# ADC-ANALOGUE_INPUT.net
KiCad netlist of a schematic drawn in Altium Designer
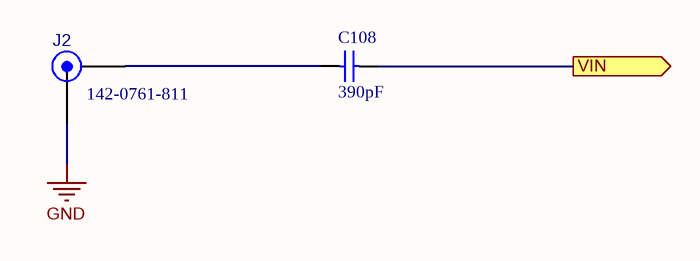
[diagram p0: ADC-ANALOGUE INPUT.SchDoc]

(export (version "E")
  (design (tool "Eeschema 10.0.6"))
  (components
    (comp (ref "C108")
      (value "390pF")
      (footprint "CAPC1005X55N")
      (description "Capacitor 0402 SMD")
      (fields (field (name "CREATED_BY") "EDA-ASA") (field (name "CHECKED_BY") "*"))
      (libsource (lib "EDA-Passive") (part "cap0402"))
    )
    (comp (ref "J2")
      (value "142-0761-811")
      (footprint "EDGE_LAUNCH_TH_SMA")
      (description "High Frequency SMA End Lauch Connector")
      (fields
        (field (name "MANUFACTURER") "JOHNSON")
        (field (name "MANUFACTURER_PN") "142-0761-811")
        (field (name "CREATED_BY") "CT")
        (field (name "CHECKED_BY") "*")
      )
      (libsource (lib "Charles-TEMP") (part "142-0761-811"))
    )
  )
  (nets
    (net (code "1") (name "/VIN") (class "Default")
      (node (ref "C108") (pin "2") (pinfunction "2_2") (pintype "passive"))
    )
    (net (code "2") (name "GND") (class "Default")
      (node (ref "J2") (pin "2") (pinfunction "2_2") (pintype "passive"))
    )
    (net (code "3") (name "Net-(C108-Pad1)") (class "Default")
      (node (ref "C108") (pin "1") (pinfunction "1_1") (pintype "passive"))
      (node (ref "J2") (pin "1") (pinfunction "1_1") (pintype "passive"))
    )
  )
)
